# P05_Processor_Page_3_of_3.net
KiCad netlist of a schematic drawn in Altium Designer
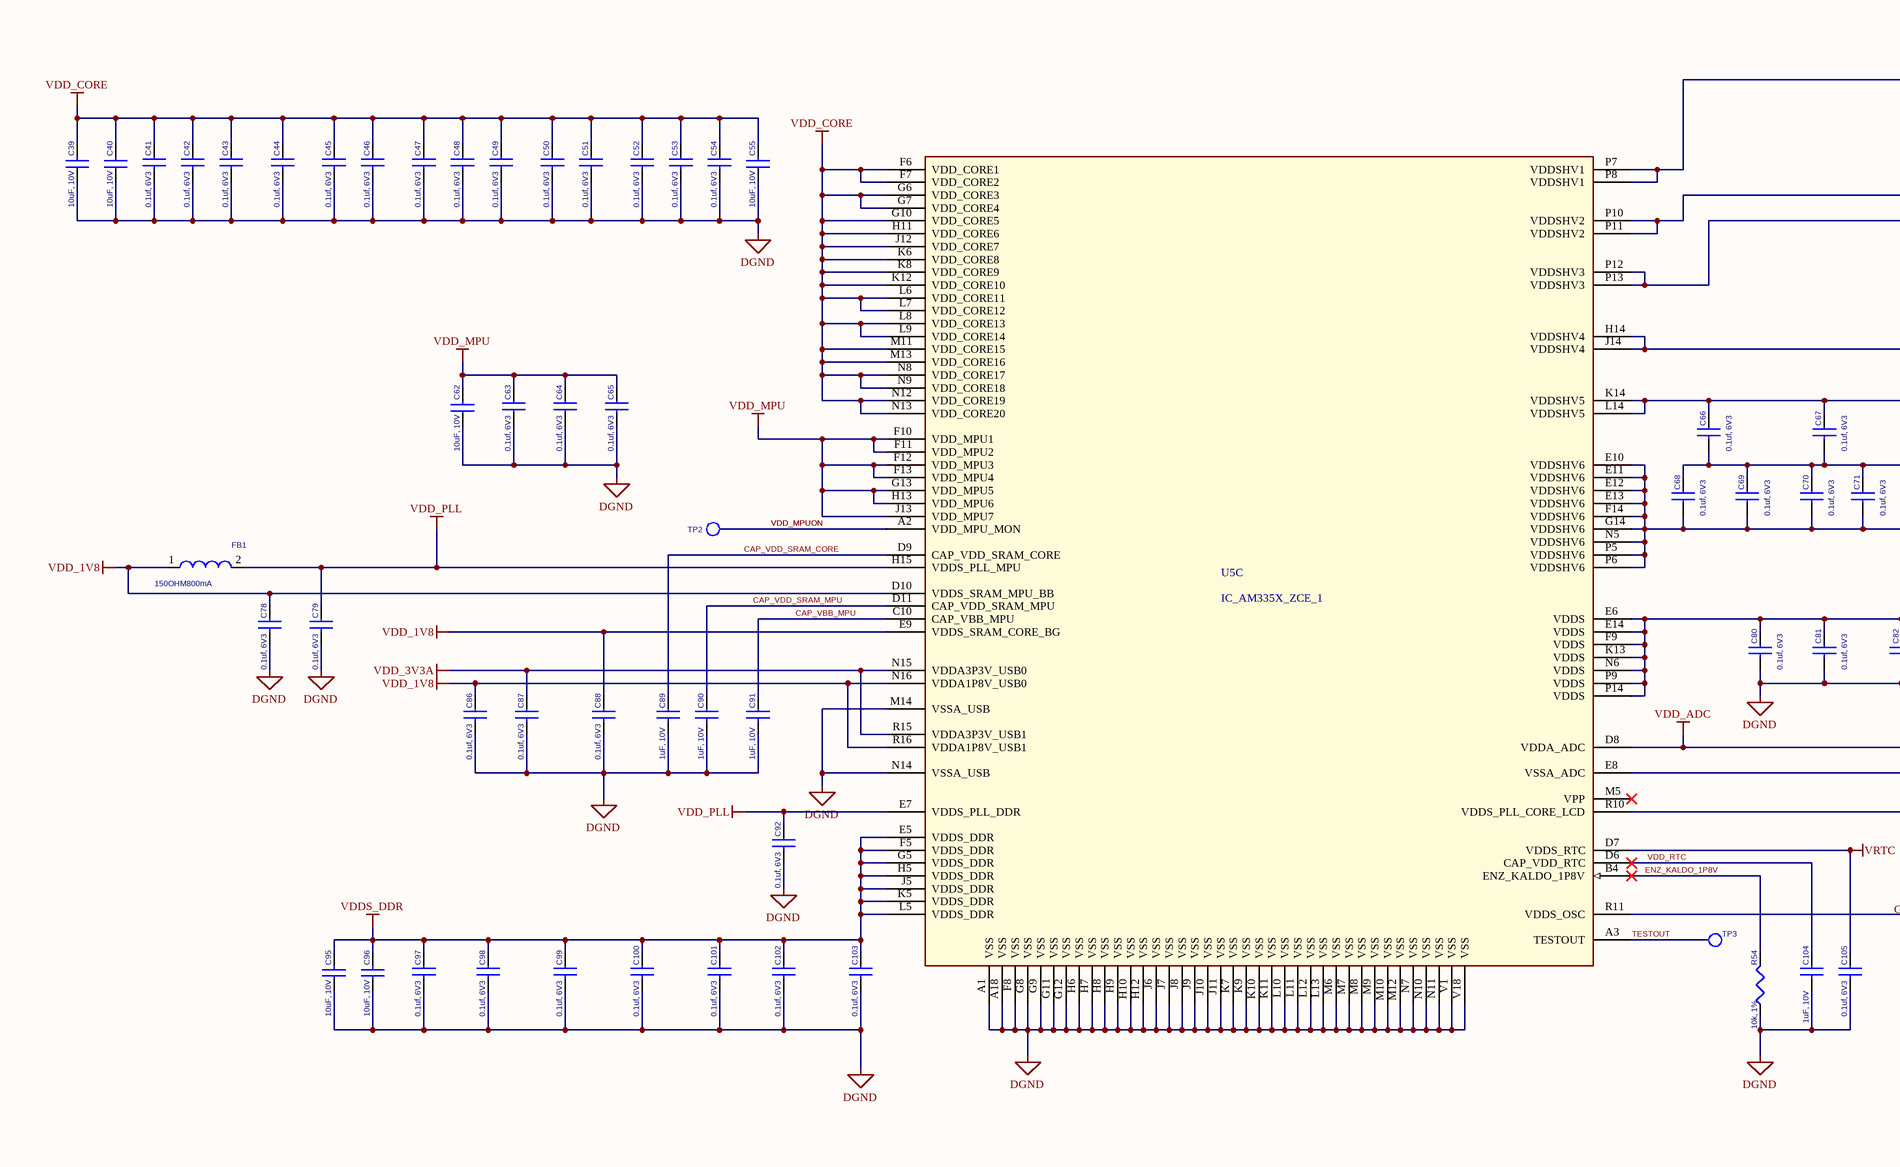
[diagram p0: P05_Processor Page 3 of 3.SchDoc, left]
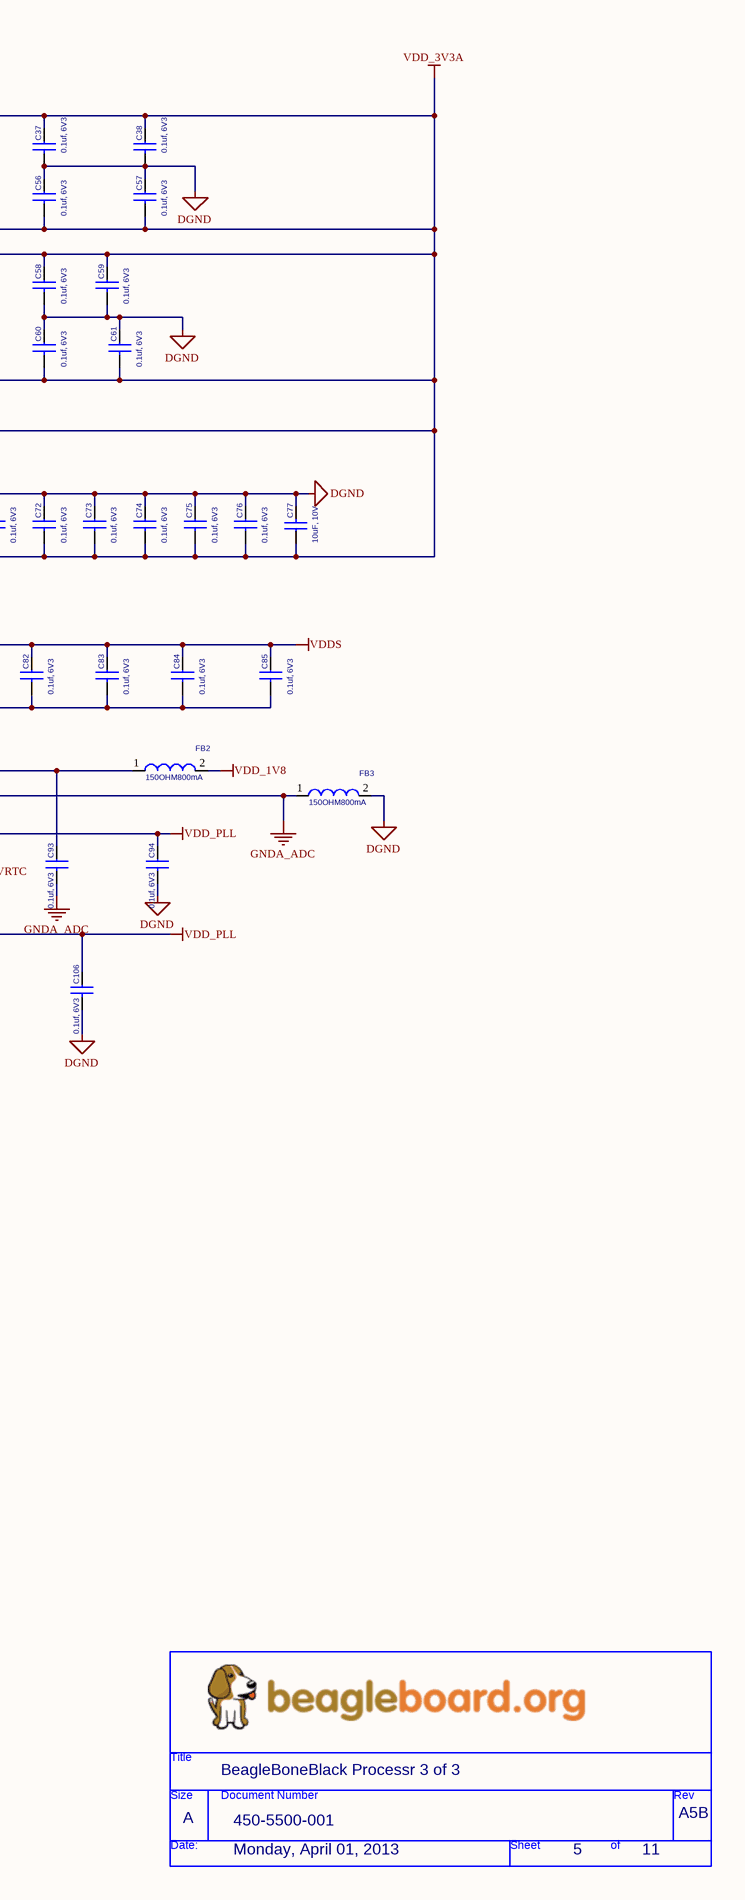
[diagram p1: P05_Processor Page 3 of 3.SchDoc, right]

(export (version "E")
  (design (tool "Eeschema 10.0.6"))
  (components
    (comp (ref "C37")
      (value "0.1uf, 6V3")
      (footprint "402")
      (description "CAP CER 0.1UF 6.3V 10% X5R 0402")
      (fields
        (field (name "MANUFACTURER") "TDK Corporation")
        (field (name "MANUFACTURER PART NUMBER") "C1005X5R0J104K050BA")
      )
      (libsource (lib "BEAGLEBONEBLACK_REV A5B") (part "CAP_0.1uF_X7R_16V_10% 0402"))
    )
    (comp (ref "C38")
      (value "0.1uf, 6V3")
      (footprint "402")
      (description "CAP CER 0.1UF 6.3V 10% X5R 0402")
      (fields
        (field (name "MANUFACTURER") "TDK Corporation")
        (field (name "MANUFACTURER PART NUMBER") "C1005X5R0J104K050BA")
      )
      (libsource (lib "BEAGLEBONEBLACK_REV A5B") (part "CAP_0.1uF_X7R_16V_10% 0402"))
    )
    (comp (ref "C39")
      (value "10uF, 10V")
      (description "CAP CER 10UF 10V Y5V 0805")
      (fields
        (field (name "MANUFACTURER") "TDK Corporation")
        (field (name "MANUFACTURER PART NUMBER") "C2012Y5V1A106Z")
      )
      (libsource (lib "BEAGLEBONEBLACK_REV A5B") (part "CAP_10uF_Y5V_10V_10%_0805"))
    )
    (comp (ref "C40")
      (value "10uF, 10V")
      (description "CAP CER 10UF 10V Y5V 0805")
      (fields
        (field (name "MANUFACTURER") "TDK Corporation")
        (field (name "MANUFACTURER PART NUMBER") "C2012Y5V1A106Z")
      )
      (libsource (lib "BEAGLEBONEBLACK_REV A5B") (part "CAP_10uF_Y5V_10V_10%_0805"))
    )
    (comp (ref "C41")
      (value "0.1uf, 6V3")
      (footprint "402")
      (description "CAP CER 0.1UF 6.3V 10% X5R 0402")
      (fields
        (field (name "MANUFACTURER") "TDK Corporation")
        (field (name "MANUFACTURER PART NUMBER") "C1005X5R0J104K050BA")
      )
      (libsource (lib "BEAGLEBONEBLACK_REV A5B") (part "CAP_0.1uF_X7R_16V_10% 0402"))
    )
    (comp (ref "C42")
      (value "0.1uf, 6V3")
      (footprint "402")
      (description "CAP CER 0.1UF 6.3V 10% X5R 0402")
      (fields
        (field (name "MANUFACTURER") "TDK Corporation")
        (field (name "MANUFACTURER PART NUMBER") "C1005X5R0J104K050BA")
      )
      (libsource (lib "BEAGLEBONEBLACK_REV A5B") (part "CAP_0.1uF_X7R_16V_10% 0402"))
    )
    (comp (ref "C43")
      (value "0.1uf, 6V3")
      (footprint "402")
      (description "CAP CER 0.1UF 6.3V 10% X5R 0402")
      (fields
        (field (name "MANUFACTURER") "TDK Corporation")
        (field (name "MANUFACTURER PART NUMBER") "C1005X5R0J104K050BA")
      )
      (libsource (lib "BEAGLEBONEBLACK_REV A5B") (part "CAP_0.1uF_X7R_16V_10% 0402"))
    )
    (comp (ref "C44")
      (value "0.1uf, 6V3")
      (footprint "402")
      (description "CAP CER 0.1UF 6.3V 10% X5R 0402")
      (fields
        (field (name "MANUFACTURER") "TDK Corporation")
        (field (name "MANUFACTURER PART NUMBER") "C1005X5R0J104K050BA")
      )
      (libsource (lib "BEAGLEBONEBLACK_REV A5B") (part "CAP_0.1uF_X7R_16V_10% 0402"))
    )
    (comp (ref "C45")
      (value "0.1uf, 6V3")
      (footprint "402")
      (description "CAP CER 0.1UF 6.3V 10% X5R 0402")
      (fields
        (field (name "MANUFACTURER") "TDK Corporation")
        (field (name "MANUFACTURER PART NUMBER") "C1005X5R0J104K050BA")
      )
      (libsource (lib "BEAGLEBONEBLACK_REV A5B") (part "CAP_0.1uF_X7R_16V_10% 0402"))
    )
    (comp (ref "C46")
      (value "0.1uf, 6V3")
      (footprint "402")
      (description "CAP CER 0.1UF 6.3V 10% X5R 0402")
      (fields
        (field (name "MANUFACTURER") "TDK Corporation")
        (field (name "MANUFACTURER PART NUMBER") "C1005X5R0J104K050BA")
      )
      (libsource (lib "BEAGLEBONEBLACK_REV A5B") (part "CAP_0.1uF_X7R_16V_10% 0402"))
    )
    (comp (ref "C47")
      (value "0.1uf, 6V3")
      (footprint "402")
      (description "CAP CER 0.1UF 6.3V 10% X5R 0402")
      (fields
        (field (name "MANUFACTURER") "TDK Corporation")
        (field (name "MANUFACTURER PART NUMBER") "C1005X5R0J104K050BA")
      )
      (libsource (lib "BEAGLEBONEBLACK_REV A5B") (part "CAP_0.1uF_X7R_16V_10% 0402"))
    )
    (comp (ref "C48")
      (value "0.1uf, 6V3")
      (footprint "402")
      (description "CAP CER 0.1UF 6.3V 10% X5R 0402")
      (fields
        (field (name "MANUFACTURER") "TDK Corporation")
        (field (name "MANUFACTURER PART NUMBER") "C1005X5R0J104K050BA")
      )
      (libsource (lib "BEAGLEBONEBLACK_REV A5B") (part "CAP_0.1uF_X7R_16V_10% 0402"))
    )
    (comp (ref "C49")
      (value "0.1uf, 6V3")
      (footprint "402")
      (description "CAP CER 0.1UF 6.3V 10% X5R 0402")
      (fields
        (field (name "MANUFACTURER") "TDK Corporation")
        (field (name "MANUFACTURER PART NUMBER") "C1005X5R0J104K050BA")
      )
      (libsource (lib "BEAGLEBONEBLACK_REV A5B") (part "CAP_0.1uF_X7R_16V_10% 0402"))
    )
    (comp (ref "C50")
      (value "0.1uf, 6V3")
      (footprint "402")
      (description "CAP CER 0.1UF 6.3V 10% X5R 0402")
      (fields
        (field (name "MANUFACTURER") "TDK Corporation")
        (field (name "MANUFACTURER PART NUMBER") "C1005X5R0J104K050BA")
      )
      (libsource (lib "BEAGLEBONEBLACK_REV A5B") (part "CAP_0.1uF_X7R_16V_10% 0402"))
    )
    (comp (ref "C51")
      (value "0.1uf, 6V3")
      (footprint "402")
      (description "CAP CER 0.1UF 6.3V 10% X5R 0402")
      (fields
        (field (name "MANUFACTURER") "TDK Corporation")
        (field (name "MANUFACTURER PART NUMBER") "C1005X5R0J104K050BA")
      )
      (libsource (lib "BEAGLEBONEBLACK_REV A5B") (part "CAP_0.1uF_X7R_16V_10% 0402"))
    )
    (comp (ref "C52")
      (value "0.1uf, 6V3")
      (footprint "402")
      (description "CAP CER 0.1UF 6.3V 10% X5R 0402")
      (fields
        (field (name "MANUFACTURER") "TDK Corporation")
        (field (name "MANUFACTURER PART NUMBER") "C1005X5R0J104K050BA")
      )
      (libsource (lib "BEAGLEBONEBLACK_REV A5B") (part "CAP_0.1uF_X7R_16V_10% 0402"))
    )
    (comp (ref "C53")
      (value "0.1uf, 6V3")
      (footprint "402")
      (description "CAP CER 0.1UF 6.3V 10% X5R 0402")
      (fields
        (field (name "MANUFACTURER") "TDK Corporation")
        (field (name "MANUFACTURER PART NUMBER") "C1005X5R0J104K050BA")
      )
      (libsource (lib "BEAGLEBONEBLACK_REV A5B") (part "CAP_0.1uF_X7R_16V_10% 0402"))
    )
    (comp (ref "C54")
      (value "0.1uf, 6V3")
      (footprint "402")
      (description "CAP CER 0.1UF 6.3V 10% X5R 0402")
      (fields
        (field (name "MANUFACTURER") "TDK Corporation")
        (field (name "MANUFACTURER PART NUMBER") "C1005X5R0J104K050BA")
      )
      (libsource (lib "BEAGLEBONEBLACK_REV A5B") (part "CAP_0.1uF_X7R_16V_10% 0402"))
    )
    (comp (ref "C55")
      (value "10uF, 10V")
      (description "CAP CER 10UF 10V Y5V 0805")
      (fields
        (field (name "MANUFACTURER") "TDK Corporation")
        (field (name "MANUFACTURER PART NUMBER") "C2012Y5V1A106Z")
      )
      (libsource (lib "BEAGLEBONEBLACK_REV A5B") (part "CAP_10uF_Y5V_10V_10%_0805"))
    )
    (comp (ref "C56")
      (value "0.1uf, 6V3")
      (footprint "402")
      (description "CAP CER 0.1UF 6.3V 10% X5R 0402")
      (fields
        (field (name "MANUFACTURER") "TDK Corporation")
        (field (name "MANUFACTURER PART NUMBER") "C1005X5R0J104K050BA")
      )
      (libsource (lib "BEAGLEBONEBLACK_REV A5B") (part "CAP_0.1uF_X7R_16V_10% 0402"))
    )
    (comp (ref "C57")
      (value "0.1uf, 6V3")
      (footprint "402")
      (description "CAP CER 0.1UF 6.3V 10% X5R 0402")
      (fields
        (field (name "MANUFACTURER") "TDK Corporation")
        (field (name "MANUFACTURER PART NUMBER") "C1005X5R0J104K050BA")
      )
      (libsource (lib "BEAGLEBONEBLACK_REV A5B") (part "CAP_0.1uF_X7R_16V_10% 0402"))
    )
    (comp (ref "C58")
      (value "0.1uf, 6V3")
      (footprint "402")
      (description "CAP CER 0.1UF 6.3V 10% X5R 0402")
      (fields
        (field (name "MANUFACTURER") "TDK Corporation")
        (field (name "MANUFACTURER PART NUMBER") "C1005X5R0J104K050BA")
      )
      (libsource (lib "BEAGLEBONEBLACK_REV A5B") (part "CAP_0.1uF_X7R_16V_10% 0402"))
    )
    (comp (ref "C59")
      (value "0.1uf, 6V3")
      (footprint "402")
      (description "CAP CER 0.1UF 6.3V 10% X5R 0402")
      (fields
        (field (name "MANUFACTURER") "TDK Corporation")
        (field (name "MANUFACTURER PART NUMBER") "C1005X5R0J104K050BA")
      )
      (libsource (lib "BEAGLEBONEBLACK_REV A5B") (part "CAP_0.1uF_X7R_16V_10% 0402"))
    )
    (comp (ref "C60")
      (value "0.1uf, 6V3")
      (footprint "402")
      (description "CAP CER 0.1UF 6.3V 10% X5R 0402")
      (fields
        (field (name "MANUFACTURER") "TDK Corporation")
        (field (name "MANUFACTURER PART NUMBER") "C1005X5R0J104K050BA")
      )
      (libsource (lib "BEAGLEBONEBLACK_REV A5B") (part "CAP_0.1uF_X7R_16V_10% 0402"))
    )
    (comp (ref "C61")
      (value "0.1uf, 6V3")
      (footprint "402")
      (description "CAP CER 0.1UF 6.3V 10% X5R 0402")
      (fields
        (field (name "MANUFACTURER") "TDK Corporation")
        (field (name "MANUFACTURER PART NUMBER") "C1005X5R0J104K050BA")
      )
      (libsource (lib "BEAGLEBONEBLACK_REV A5B") (part "CAP_0.1uF_X7R_16V_10% 0402"))
    )
    (comp (ref "C62")
      (value "10uF, 10V")
      (description "CAP CER 10UF 10V Y5V 0805")
      (fields
        (field (name "MANUFACTURER") "TDK Corporation")
        (field (name "MANUFACTURER PART NUMBER") "C2012Y5V1A106Z")
      )
      (libsource (lib "BEAGLEBONEBLACK_REV A5B") (part "CAP_10uF_Y5V_10V_10%_0805"))
    )
    (comp (ref "C63")
      (value "0.1uf, 6V3")
      (footprint "402")
      (description "CAP CER 0.1UF 6.3V 10% X5R 0402")
      (fields
        (field (name "MANUFACTURER") "TDK Corporation")
        (field (name "MANUFACTURER PART NUMBER") "C1005X5R0J104K050BA")
      )
      (libsource (lib "BEAGLEBONEBLACK_REV A5B") (part "CAP_0.1uF_X7R_16V_10% 0402"))
    )
    (comp (ref "C64")
      (value "0.1uf, 6V3")
      (footprint "402")
      (description "CAP CER 0.1UF 6.3V 10% X5R 0402")
      (fields
        (field (name "MANUFACTURER") "TDK Corporation")
        (field (name "MANUFACTURER PART NUMBER") "C1005X5R0J104K050BA")
      )
      (libsource (lib "BEAGLEBONEBLACK_REV A5B") (part "CAP_0.1uF_X7R_16V_10% 0402"))
    )
    (comp (ref "C65")
      (value "0.1uf, 6V3")
      (footprint "402")
      (description "CAP CER 0.1UF 6.3V 10% X5R 0402")
      (fields
        (field (name "MANUFACTURER") "TDK Corporation")
        (field (name "MANUFACTURER PART NUMBER") "C1005X5R0J104K050BA")
      )
      (libsource (lib "BEAGLEBONEBLACK_REV A5B") (part "CAP_0.1uF_X7R_16V_10% 0402"))
    )
    (comp (ref "C66")
      (value "0.1uf, 6V3")
      (footprint "402")
      (description "CAP CER 0.1UF 6.3V 10% X5R 0402")
      (fields
        (field (name "MANUFACTURER") "TDK Corporation")
        (field (name "MANUFACTURER PART NUMBER") "C1005X5R0J104K050BA")
      )
      (libsource (lib "BEAGLEBONEBLACK_REV A5B") (part "CAP_0.1uF_X7R_16V_10% 0402"))
    )
    (comp (ref "C67")
      (value "0.1uf, 6V3")
      (footprint "402")
      (description "CAP CER 0.1UF 6.3V 10% X5R 0402")
      (fields
        (field (name "MANUFACTURER") "TDK Corporation")
        (field (name "MANUFACTURER PART NUMBER") "C1005X5R0J104K050BA")
      )
      (libsource (lib "BEAGLEBONEBLACK_REV A5B") (part "CAP_0.1uF_X7R_16V_10% 0402"))
    )
    (comp (ref "C68")
      (value "0.1uf, 6V3")
      (footprint "402")
      (description "CAP CER 0.1UF 6.3V 10% X5R 0402")
      (fields
        (field (name "MANUFACTURER") "TDK Corporation")
        (field (name "MANUFACTURER PART NUMBER") "C1005X5R0J104K050BA")
      )
      (libsource (lib "BEAGLEBONEBLACK_REV A5B") (part "CAP_0.1uF_X7R_16V_10% 0402"))
    )
    (comp (ref "C69")
      (value "0.1uf, 6V3")
      (footprint "402")
      (description "CAP CER 0.1UF 6.3V 10% X5R 0402")
      (fields
        (field (name "MANUFACTURER") "TDK Corporation")
        (field (name "MANUFACTURER PART NUMBER") "C1005X5R0J104K050BA")
      )
      (libsource (lib "BEAGLEBONEBLACK_REV A5B") (part "CAP_0.1uF_X7R_16V_10% 0402"))
    )
    (comp (ref "C70")
      (value "0.1uf, 6V3")
      (footprint "402")
      (description "CAP CER 0.1UF 6.3V 10% X5R 0402")
      (fields
        (field (name "MANUFACTURER") "TDK Corporation")
        (field (name "MANUFACTURER PART NUMBER") "C1005X5R0J104K050BA")
      )
      (libsource (lib "BEAGLEBONEBLACK_REV A5B") (part "CAP_0.1uF_X7R_16V_10% 0402"))
    )
    (comp (ref "C71")
      (value "0.1uf, 6V3")
      (footprint "402")
      (description "CAP CER 0.1UF 6.3V 10% X5R 0402")
      (fields
        (field (name "MANUFACTURER") "TDK Corporation")
        (field (name "MANUFACTURER PART NUMBER") "C1005X5R0J104K050BA")
      )
      (libsource (lib "BEAGLEBONEBLACK_REV A5B") (part "CAP_0.1uF_X7R_16V_10% 0402"))
    )
    (comp (ref "C72")
      (value "0.1uf, 6V3")
      (footprint "402")
      (description "CAP CER 0.1UF 6.3V 10% X5R 0402")
      (fields
        (field (name "MANUFACTURER") "TDK Corporation")
        (field (name "MANUFACTURER PART NUMBER") "C1005X5R0J104K050BA")
      )
      (libsource (lib "BEAGLEBONEBLACK_REV A5B") (part "CAP_0.1uF_X7R_16V_10% 0402"))
    )
    (comp (ref "C73")
      (value "0.1uf, 6V3")
      (footprint "402")
      (description "CAP CER 0.1UF 6.3V 10% X5R 0402")
      (fields
        (field (name "MANUFACTURER") "TDK Corporation")
        (field (name "MANUFACTURER PART NUMBER") "C1005X5R0J104K050BA")
      )
      (libsource (lib "BEAGLEBONEBLACK_REV A5B") (part "CAP_0.1uF_X7R_16V_10% 0402"))
    )
    (comp (ref "C74")
      (value "0.1uf, 6V3")
      (footprint "402")
      (description "CAP CER 0.1UF 6.3V 10% X5R 0402")
      (fields
        (field (name "MANUFACTURER") "TDK Corporation")
        (field (name "MANUFACTURER PART NUMBER") "C1005X5R0J104K050BA")
      )
      (libsource (lib "BEAGLEBONEBLACK_REV A5B") (part "CAP_0.1uF_X7R_16V_10% 0402"))
    )
    (comp (ref "C75")
      (value "0.1uf, 6V3")
      (footprint "402")
      (description "CAP CER 0.1UF 6.3V 10% X5R 0402")
      (fields
        (field (name "MANUFACTURER") "TDK Corporation")
        (field (name "MANUFACTURER PART NUMBER") "C1005X5R0J104K050BA")
      )
      (libsource (lib "BEAGLEBONEBLACK_REV A5B") (part "CAP_0.1uF_X7R_16V_10% 0402"))
    )
    (comp (ref "C76")
      (value "0.1uf, 6V3")
      (footprint "402")
      (description "CAP CER 0.1UF 6.3V 10% X5R 0402")
      (fields
        (field (name "MANUFACTURER") "TDK Corporation")
        (field (name "MANUFACTURER PART NUMBER") "C1005X5R0J104K050BA")
      )
      (libsource (lib "BEAGLEBONEBLACK_REV A5B") (part "CAP_0.1uF_X7R_16V_10% 0402"))
    )
    (comp (ref "C77")
      (value "10uF, 10V")
      (description "CAP CER 10UF 10V Y5V 0805")
      (fields
        (field (name "MANUFACTURER") "TDK Corporation")
        (field (name "MANUFACTURER PART NUMBER") "C2012Y5V1A106Z")
      )
      (libsource (lib "BEAGLEBONEBLACK_REV A5B") (part "CAP_10uF_Y5V_10V_10%_0805"))
    )
    (comp (ref "C78")
      (value "0.1uf, 6V3")
      (footprint "402")
      (description "CAP CER 0.1UF 6.3V 10% X5R 0402")
      (fields
        (field (name "MANUFACTURER") "TDK Corporation")
        (field (name "MANUFACTURER PART NUMBER") "C1005X5R0J104K050BA")
      )
      (libsource (lib "BEAGLEBONEBLACK_REV A5B") (part "CAP_0.1uF_X7R_16V_10% 0402"))
    )
    (comp (ref "C79")
      (value "0.1uf, 6V3")
      (footprint "402")
      (description "CAP CER 0.1UF 6.3V 10% X5R 0402")
      (fields
        (field (name "MANUFACTURER") "TDK Corporation")
        (field (name "MANUFACTURER PART NUMBER") "C1005X5R0J104K050BA")
      )
      (libsource (lib "BEAGLEBONEBLACK_REV A5B") (part "CAP_0.1uF_X7R_16V_10% 0402"))
    )
    (comp (ref "C80")
      (value "0.1uf, 6V3")
      (footprint "402")
      (description "CAP CER 0.1UF 6.3V 10% X5R 0402")
      (fields
        (field (name "MANUFACTURER") "TDK Corporation")
        (field (name "MANUFACTURER PART NUMBER") "C1005X5R0J104K050BA")
      )
      (libsource (lib "BEAGLEBONEBLACK_REV A5B") (part "CAP_0.1uF_X7R_16V_10% 0402"))
    )
    (comp (ref "C81")
      (value "0.1uf, 6V3")
      (footprint "402")
      (description "CAP CER 0.1UF 6.3V 10% X5R 0402")
      (fields
        (field (name "MANUFACTURER") "TDK Corporation")
        (field (name "MANUFACTURER PART NUMBER") "C1005X5R0J104K050BA")
      )
      (libsource (lib "BEAGLEBONEBLACK_REV A5B") (part "CAP_0.1uF_X7R_16V_10% 0402"))
    )
    (comp (ref "C82")
      (value "0.1uf, 6V3")
      (footprint "402")
      (description "CAP CER 0.1UF 6.3V 10% X5R 0402")
      (fields
        (field (name "MANUFACTURER") "TDK Corporation")
        (field (name "MANUFACTURER PART NUMBER") "C1005X5R0J104K050BA")
      )
      (libsource (lib "BEAGLEBONEBLACK_REV A5B") (part "CAP_0.1uF_X7R_16V_10% 0402"))
    )
    (comp (ref "C83")
      (value "0.1uf, 6V3")
      (footprint "402")
      (description "CAP CER 0.1UF 6.3V 10% X5R 0402")
      (fields
        (field (name "MANUFACTURER") "TDK Corporation")
        (field (name "MANUFACTURER PART NUMBER") "C1005X5R0J104K050BA")
      )
      (libsource (lib "BEAGLEBONEBLACK_REV A5B") (part "CAP_0.1uF_X7R_16V_10% 0402"))
    )
    (comp (ref "C84")
      (value "0.1uf, 6V3")
      (footprint "402")
      (description "CAP CER 0.1UF 6.3V 10% X5R 0402")
      (fields
        (field (name "MANUFACTURER") "TDK Corporation")
        (field (name "MANUFACTURER PART NUMBER") "C1005X5R0J104K050BA")
      )
      (libsource (lib "BEAGLEBONEBLACK_REV A5B") (part "CAP_0.1uF_X7R_16V_10% 0402"))
    )
    (comp (ref "C85")
      (value "0.1uf, 6V3")
      (footprint "402")
      (description "CAP CER 0.1UF 6.3V 10% X5R 0402")
      (fields
        (field (name "MANUFACTURER") "TDK Corporation")
        (field (name "MANUFACTURER PART NUMBER") "C1005X5R0J104K050BA")
      )
      (libsource (lib "BEAGLEBONEBLACK_REV A5B") (part "CAP_0.1uF_X7R_16V_10% 0402"))
    )
    (comp (ref "C86")
      (value "0.1uf, 6V3")
      (footprint "402")
      (description "CAP CER 0.1UF 6.3V 10% X5R 0402")
      (fields
        (field (name "MANUFACTURER") "TDK Corporation")
        (field (name "MANUFACTURER PART NUMBER") "C1005X5R0J104K050BA")
      )
      (libsource (lib "BEAGLEBONEBLACK_REV A5B") (part "CAP_0.1uF_X7R_16V_10% 0402"))
    )
    (comp (ref "C87")
      (value "0.1uf, 6V3")
      (footprint "402")
      (description "CAP CER 0.1UF 6.3V 10% X5R 0402")
      (fields
        (field (name "MANUFACTURER") "TDK Corporation")
        (field (name "MANUFACTURER PART NUMBER") "C1005X5R0J104K050BA")
      )
      (libsource (lib "BEAGLEBONEBLACK_REV A5B") (part "CAP_0.1uF_X7R_16V_10% 0402"))
    )
    (comp (ref "C88")
      (value "0.1uf, 6V3")
      (footprint "402")
      (description "CAP CER 0.1UF 6.3V 10% X5R 0402")
      (fields
        (field (name "MANUFACTURER") "TDK Corporation")
        (field (name "MANUFACTURER PART NUMBER") "C1005X5R0J104K050BA")
      )
      (libsource (lib "BEAGLEBONEBLACK_REV A5B") (part "CAP_0.1uF_X7R_16V_10% 0402"))
    )
    (comp (ref "C89")
      (value "1uF, 10V")
      (footprint "402")
      (description "CAP CER 1UF 10V 10% X5R 0402")
      (fields
        (field (name "MANUFACTURER") "AVX Corporation")
        (field (name "MANUFACTURER PART NUMBER") "0402ZD105KAT2A")
      )
      (libsource (lib "BEAGLEBONEBLACK_REV A5B") (part "CAP_1.0UF_X5R_10V_10%_0402"))
    )
    (comp (ref "C90")
      (value "1uF, 10V")
      (footprint "402")
      (description "CAP CER 1UF 10V 10% X5R 0402")
      (fields
        (field (name "MANUFACTURER") "AVX Corporation")
        (field (name "MANUFACTURER PART NUMBER") "0402ZD105KAT2A")
      )
      (libsource (lib "BEAGLEBONEBLACK_REV A5B") (part "CAP_1.0UF_X5R_10V_10%_0402"))
    )
    (comp (ref "C91")
      (value "1uF, 10V")
      (footprint "402")
      (description "CAP CER 1UF 10V 10% X5R 0402")
      (fields
        (field (name "MANUFACTURER") "AVX Corporation")
        (field (name "MANUFACTURER PART NUMBER") "0402ZD105KAT2A")
      )
      (libsource (lib "BEAGLEBONEBLACK_REV A5B") (part "CAP_1.0UF_X5R_10V_10%_0402"))
    )
    (comp (ref "C92")
      (value "0.1uf, 6V3")
      (footprint "402")
      (description "CAP CER 0.1UF 6.3V 10% X5R 0402")
      (fields
        (field (name "MANUFACTURER") "TDK Corporation")
        (field (name "MANUFACTURER PART NUMBER") "C1005X5R0J104K050BA")
      )
      (libsource (lib "BEAGLEBONEBLACK_REV A5B") (part "CAP_0.1uF_X7R_16V_10% 0402"))
    )
    (comp (ref "C93")
      (value "0.1uf, 6V3")
      (footprint "402")
      (description "CAP CER 0.1UF 6.3V 10% X5R 0402")
      (fields
        (field (name "MANUFACTURER") "TDK Corporation")
        (field (name "MANUFACTURER PART NUMBER") "C1005X5R0J104K050BA")
      )
      (libsource (lib "BEAGLEBONEBLACK_REV A5B") (part "CAP_0.1uF_X7R_16V_10% 0402"))
    )
    (comp (ref "C94")
      (value "0.1uf, 6V3")
      (footprint "402")
      (description "CAP CER 0.1UF 6.3V 10% X5R 0402")
      (fields
        (field (name "MANUFACTURER") "TDK Corporation")
        (field (name "MANUFACTURER PART NUMBER") "C1005X5R0J104K050BA")
      )
      (libsource (lib "BEAGLEBONEBLACK_REV A5B") (part "CAP_0.1uF_X7R_16V_10% 0402"))
    )
    (comp (ref "C95")
      (value "10uF, 10V")
      (description "CAP CER 10UF 10V Y5V 0805")
      (fields
        (field (name "MANUFACTURER") "TDK Corporation")
        (field (name "MANUFACTURER PART NUMBER") "C2012Y5V1A106Z")
      )
      (libsource (lib "BEAGLEBONEBLACK_REV A5B") (part "CAP_10uF_Y5V_10V_10%_0805"))
    )
    (comp (ref "C96")
      (value "10uF, 10V")
      (description "CAP CER 10UF 10V Y5V 0805")
      (fields
        (field (name "MANUFACTURER") "TDK Corporation")
        (field (name "MANUFACTURER PART NUMBER") "C2012Y5V1A106Z")
      )
      (libsource (lib "BEAGLEBONEBLACK_REV A5B") (part "CAP_10uF_Y5V_10V_10%_0805"))
    )
    (comp (ref "C97")
      (value "0.1uf, 6V3")
      (footprint "402")
      (description "CAP CER 0.1UF 6.3V 10% X5R 0402")
      (fields
        (field (name "MANUFACTURER") "TDK Corporation")
        (field (name "MANUFACTURER PART NUMBER") "C1005X5R0J104K050BA")
      )
      (libsource (lib "BEAGLEBONEBLACK_REV A5B") (part "CAP_0.1uF_X7R_16V_10% 0402"))
    )
    (comp (ref "C98")
      (value "0.1uf, 6V3")
      (footprint "402")
      (description "CAP CER 0.1UF 6.3V 10% X5R 0402")
      (fields
        (field (name "MANUFACTURER") "TDK Corporation")
        (field (name "MANUFACTURER PART NUMBER") "C1005X5R0J104K050BA")
      )
      (libsource (lib "BEAGLEBONEBLACK_REV A5B") (part "CAP_0.1uF_X7R_16V_10% 0402"))
    )
    (comp (ref "C99")
      (value "0.1uf, 6V3")
      (footprint "402")
      (description "CAP CER 0.1UF 6.3V 10% X5R 0402")
      (fields
        (field (name "MANUFACTURER") "TDK Corporation")
        (field (name "MANUFACTURER PART NUMBER") "C1005X5R0J104K050BA")
      )
      (libsource (lib "BEAGLEBONEBLACK_REV A5B") (part "CAP_0.1uF_X7R_16V_10% 0402"))
    )
    (comp (ref "C100")
      (value "0.1uf, 6V3")
      (footprint "402")
      (description "CAP CER 0.1UF 6.3V 10% X5R 0402")
      (fields
        (field (name "MANUFACTURER") "TDK Corporation")
        (field (name "MANUFACTURER PART NUMBER") "C1005X5R0J104K050BA")
      )
      (libsource (lib "BEAGLEBONEBLACK_REV A5B") (part "CAP_0.1uF_X7R_16V_10% 0402"))
    )
    (comp (ref "C101")
      (value "0.1uf, 6V3")
      (footprint "402")
      (description "CAP CER 0.1UF 6.3V 10% X5R 0402")
      (fields
        (field (name "MANUFACTURER") "TDK Corporation")
        (field (name "MANUFACTURER PART NUMBER") "C1005X5R0J104K050BA")
      )
      (libsource (lib "BEAGLEBONEBLACK_REV A5B") (part "CAP_0.1uF_X7R_16V_10% 0402"))
    )
    (comp (ref "C102")
      (value "0.1uf, 6V3")
      (footprint "402")
      (description "CAP CER 0.1UF 6.3V 10% X5R 0402")
      (fields
        (field (name "MANUFACTURER") "TDK Corporation")
        (field (name "MANUFACTURER PART NUMBER") "C1005X5R0J104K050BA")
      )
      (libsource (lib "BEAGLEBONEBLACK_REV A5B") (part "CAP_0.1uF_X7R_16V_10% 0402"))
    )
    (comp (ref "C103")
      (value "0.1uf, 6V3")
      (footprint "402")
      (description "CAP CER 0.1UF 6.3V 10% X5R 0402")
      (fields
        (field (name "MANUFACTURER") "TDK Corporation")
        (field (name "MANUFACTURER PART NUMBER") "C1005X5R0J104K050BA")
      )
      (libsource (lib "BEAGLEBONEBLACK_REV A5B") (part "CAP_0.1uF_X7R_16V_10% 0402"))
    )
    (comp (ref "C104")
      (value "1uF, 10V")
      (footprint "402")
      (description "CAP CER 1UF 10V 10% X5R 0402")
      (fields
        (field (name "MANUFACTURER") "AVX Corporation")
        (field (name "MANUFACTURER PART NUMBER") "0402ZD105KAT2A")
      )
      (libsource (lib "BEAGLEBONEBLACK_REV A5B") (part "CAP_1.0UF_X5R_10V_10%_0402"))
    )
    (comp (ref "C105")
      (value "0.1uf, 6V3")
      (footprint "402")
      (description "CAP CER 0.1UF 6.3V 10% X5R 0402")
      (fields
        (field (name "MANUFACTURER") "TDK Corporation")
        (field (name "MANUFACTURER PART NUMBER") "C1005X5R0J104K050BA")
      )
      (libsource (lib "BEAGLEBONEBLACK_REV A5B") (part "CAP_0.1uF_X7R_16V_10% 0402"))
    )
    (comp (ref "C106")
      (value "0.1uf, 6V3")
      (footprint "402")
      (description "CAP CER 0.1UF 6.3V 10% X5R 0402")
      (fields
        (field (name "MANUFACTURER") "TDK Corporation")
        (field (name "MANUFACTURER PART NUMBER") "C1005X5R0J104K050BA")
      )
      (libsource (lib "BEAGLEBONEBLACK_REV A5B") (part "CAP_0.1uF_X7R_16V_10% 0402"))
    )
    (comp (ref "FB1")
      (value "150OHM800mA")
      (footprint "SM-7351-IND-0805")
      (description "FERRITE 800MA 150 OHM 0805 SMD")
      (fields (field (name "MFR") "Steward") (field (name "TIINTPARTNUMBER") "1L0010"))
      (libsource (lib "BEAGLEBONEBLACK_REV A5B") (part "FER_180_200_0"))
    )
    (comp (ref "FB2")
      (value "150OHM800mA")
      (footprint "SM-7351-IND-0805")
      (description "FERRITE 800MA 150 OHM 0805 SMD")
      (fields (field (name "MFR") "Steward") (field (name "TIINTPARTNUMBER") "1L0010"))
      (libsource (lib "BEAGLEBONEBLACK_REV A5B") (part "FER_180_200_0"))
    )
    (comp (ref "FB3")
      (value "150OHM800mA")
      (footprint "SM-7351-IND-0805")
      (description "FERRITE 800MA 150 OHM 0805 SMD")
      (fields (field (name "MFR") "Steward") (field (name "TIINTPARTNUMBER") "1L0010"))
      (libsource (lib "BEAGLEBONEBLACK_REV A5B") (part "FER_180_200_0"))
    )
    (comp (ref "R54")
      (value "10k, 1%")
      (footprint "402")
      (description "RES 10K OHM 1/16W 5% 0402 SMD")
      (fields
        (field (name "MANUFACTURER") "Rohm Semiconductor")
        (field (name "MANUFACTURER PART NUMBER") "MCR01MZPJ103")
      )
      (libsource (lib "BEAGLEBONEBLACK_REV A5B") (part "RES_10K_1/16W_1%_0402"))
    )
    (comp (ref "TP2") (value "TESTPT1") (libsource (lib "BEAGLEBONEBLACK_REV A5B") (part "TESTPT1")))
    (comp (ref "TP3") (value "TESTPT1") (libsource (lib "BEAGLEBONEBLACK_REV A5B") (part "TESTPT1")))
    (comp (ref "U5")
      (value "IC_AM335X_ZCE_1")
      (footprint "am33xx_15x15")
      (description "SubArctic Cortex A8 Processor 15x15")
      (fields (field (name "MFR") "TI") (field (name "TIINTPARTNUMBER") "1A0242"))
      (libsource (lib "BEAGLEBONEBLACK_REV A5B") (part "IC_AM335X_ZCE_1"))
    )
  )
  (nets
    (net (code "1") (name "/CAP_VBB_MPU") (class "Default")
      (node (ref "C91") (pin "1") (pinfunction "1_1") (pintype "passive"))
      (node (ref "U5") (pin "C10") (pinfunction "CAP_VBB_MPU_C10") (pintype "passive"))
    )
    (net (code "2") (name "/CAP_VDD_SRAM_CORE") (class "Default")
      (node (ref "C89") (pin "1") (pinfunction "1_1") (pintype "passive"))
      (node (ref "U5") (pin "D9") (pinfunction "CAP_VDD_SRAM_CORE_D9") (pintype "power_in"))
    )
    (net (code "3") (name "/CAP_VDD_SRAM_MPU") (class "Default")
      (node (ref "C90") (pin "1") (pinfunction "1_1") (pintype "passive"))
      (node (ref "U5") (pin "D11") (pinfunction "CAP_VDD_SRAM_MPU_D11") (pintype "power_in"))
    )
    (net (code "4") (name "/ENZ_KALDO_1P8V") (class "Default")
      (node (ref "R54") (pin "2") (pinfunction "2_2") (pintype "passive"))
      (node (ref "U5") (pin "B4") (pinfunction "ENZ_KALDO_1P8V_B4") (pintype "input"))
    )
    (net (code "5") (name "/TESTOUT") (class "Default")
      (node (ref "TP3") (pin "1") (pinfunction "TP_1") (pintype "passive"))
      (node (ref "U5") (pin "A3") (pinfunction "TESTOUT_A3") (pintype "passive"))
    )
    (net (code "6") (name "/VDD_MPUON") (class "Default")
      (node (ref "TP2") (pin "1") (pinfunction "TP_1") (pintype "passive"))
      (node (ref "U5") (pin "A2") (pinfunction "VDD_MPU_MON_A2") (pintype "passive"))
    )
    (net (code "7") (name "/VDD_RTC") (class "Default")
      (node (ref "C104") (pin "1") (pinfunction "1_1") (pintype "passive"))
      (node (ref "U5") (pin "D6") (pinfunction "CAP_VDD_RTC_D6") (pintype "power_in"))
    )
    (net (code "8") (name "DGND") (class "Default")
      (node (ref "C100") (pin "2") (pinfunction "2_2") (pintype "passive"))
      (node (ref "C101") (pin "2") (pinfunction "2_2") (pintype "passive"))
      (node (ref "C102") (pin "2") (pinfunction "2_2") (pintype "passive"))
      (node (ref "C103") (pin "2") (pinfunction "2_2") (pintype "passive"))
      (node (ref "C104") (pin "2") (pinfunction "2_2") (pintype "passive"))
      (node (ref "C105") (pin "2") (pinfunction "2_2") (pintype "passive"))
      (node (ref "C106") (pin "2") (pinfunction "2_2") (pintype "passive"))
      (node (ref "C37") (pin "2") (pinfunction "2_2") (pintype "passive"))
      (node (ref "C38") (pin "2") (pinfunction "2_2") (pintype "passive"))
      (node (ref "C39") (pin "1") (pinfunction "1_1") (pintype "passive"))
      (node (ref "C40") (pin "1") (pinfunction "1_1") (pintype "passive"))
      (node (ref "C41") (pin "2") (pinfunction "2_2") (pintype "passive"))
      (node (ref "C42") (pin "2") (pinfunction "2_2") (pintype "passive"))
      (node (ref "C43") (pin "2") (pinfunction "2_2") (pintype "passive"))
      (node (ref "C44") (pin "2") (pinfunction "2_2") (pintype "passive"))
      (node (ref "C45") (pin "2") (pinfunction "2_2") (pintype "passive"))
      (node (ref "C46") (pin "2") (pinfunction "2_2") (pintype "passive"))
      (node (ref "C47") (pin "2") (pinfunction "2_2") (pintype "passive"))
      (node (ref "C48") (pin "2") (pinfunction "2_2") (pintype "passive"))
      (node (ref "C49") (pin "2") (pinfunction "2_2") (pintype "passive"))
      (node (ref "C50") (pin "2") (pinfunction "2_2") (pintype "passive"))
      (node (ref "C51") (pin "2") (pinfunction "2_2") (pintype "passive"))
      (node (ref "C52") (pin "2") (pinfunction "2_2") (pintype "passive"))
      (node (ref "C53") (pin "2") (pinfunction "2_2") (pintype "passive"))
      (node (ref "C54") (pin "2") (pinfunction "2_2") (pintype "passive"))
      (node (ref "C55") (pin "1") (pinfunction "1_1") (pintype "passive"))
      (node (ref "C56") (pin "1") (pinfunction "1_1") (pintype "passive"))
      (node (ref "C57") (pin "1") (pinfunction "1_1") (pintype "passive"))
      (node (ref "C58") (pin "2") (pinfunction "2_2") (pintype "passive"))
      (node (ref "C59") (pin "2") (pinfunction "2_2") (pintype "passive"))
      (node (ref "C60") (pin "1") (pinfunction "1_1") (pintype "passive"))
      (node (ref "C61") (pin "1") (pinfunction "1_1") (pintype "passive"))
      (node (ref "C62") (pin "1") (pinfunction "1_1") (pintype "passive"))
      (node (ref "C63") (pin "2") (pinfunction "2_2") (pintype "passive"))
      (node (ref "C64") (pin "2") (pinfunction "2_2") (pintype "passive"))
      (node (ref "C65") (pin "2") (pinfunction "2_2") (pintype "passive"))
      (node (ref "C66") (pin "2") (pinfunction "2_2") (pintype "passive"))
      (node (ref "C67") (pin "2") (pinfunction "2_2") (pintype "passive"))
      (node (ref "C68") (pin "1") (pinfunction "1_1") (pintype "passive"))
      (node (ref "C69") (pin "1") (pinfunction "1_1") (pintype "passive"))
      (node (ref "C70") (pin "1") (pinfunction "1_1") (pintype "passive"))
      (node (ref "C71") (pin "1") (pinfunction "1_1") (pintype "passive"))
      (node (ref "C72") (pin "1") (pinfunction "1_1") (pintype "passive"))
      (node (ref "C73") (pin "1") (pinfunction "1_1") (pintype "passive"))
      (node (ref "C74") (pin "1") (pinfunction "1_1") (pintype "passive"))
      (node (ref "C75") (pin "1") (pinfunction "1_1") (pintype "passive"))
      (node (ref "C76") (pin "1") (pinfunction "1_1") (pintype "passive"))
      (node (ref "C77") (pin "2") (pinfunction "2_2") (pintype "passive"))
      (node (ref "C78") (pin "2") (pinfunction "2_2") (pintype "passive"))
      (node (ref "C79") (pin "2") (pinfunction "2_2") (pintype "passive"))
      (node (ref "C80") (pin "2") (pinfunction "2_2") (pintype "passive"))
      (node (ref "C81") (pin "2") (pinfunction "2_2") (pintype "passive"))
      (node (ref "C82") (pin "2") (pinfunction "2_2") (pintype "passive"))
      (node (ref "C83") (pin "2") (pinfunction "2_2") (pintype "passive"))
      (node (ref "C84") (pin "2") (pinfunction "2_2") (pintype "passive"))
      (node (ref "C85") (pin "2") (pinfunction "2_2") (pintype "passive"))
      (node (ref "C86") (pin "2") (pinfunction "2_2") (pintype "passive"))
      (node (ref "C87") (pin "2") (pinfunction "2_2") (pintype "passive"))
      (node (ref "C88") (pin "2") (pinfunction "2_2") (pintype "passive"))
      (node (ref "C89") (pin "2") (pinfunction "2_2") (pintype "passive"))
      (node (ref "C90") (pin "2") (pinfunction "2_2") (pintype "passive"))
      (node (ref "C91") (pin "2") (pinfunction "2_2") (pintype "passive"))
      (node (ref "C92") (pin "2") (pinfunction "2_2") (pintype "passive"))
      (node (ref "C94") (pin "2") (pinfunction "2_2") (pintype "passive"))
      (node (ref "C95") (pin "1") (pinfunction "1_1") (pintype "passive"))
      (node (ref "C96") (pin "1") (pinfunction "1_1") (pintype "passive"))
      (node (ref "C97") (pin "2") (pinfunction "2_2") (pintype "passive"))
      (node (ref "C98") (pin "2") (pinfunction "2_2") (pintype "passive"))
      (node (ref "C99") (pin "2") (pinfunction "2_2") (pintype "passive"))
      (node (ref "FB3") (pin "2") (pinfunction "2_2") (pintype "passive"))
      (node (ref "R54") (pin "1") (pinfunction "1_1") (pintype "passive"))
      (node (ref "U5") (pin "A1") (pinfunction "VSS_A1") (pintype "power_in"))
      (node (ref "U5") (pin "A18") (pinfunction "VSS_A18") (pintype "power_in"))
      (node (ref "U5") (pin "F8") (pinfunction "VSS_F8") (pintype "power_in"))
      (node (ref "U5") (pin "G11") (pinfunction "VSS_G11") (pintype "power_in"))
      (node (ref "U5") (pin "G12") (pinfunction "VSS_G12") (pintype "power_in"))
      (node (ref "U5") (pin "G8") (pinfunction "VSS_G8") (pintype "power_in"))
      (node (ref "U5") (pin "G9") (pinfunction "VSS_G9") (pintype "power_in"))
      (node (ref "U5") (pin "H10") (pinfunction "VSS_H10") (pintype "power_in"))
      (node (ref "U5") (pin "H12") (pinfunction "VSS_H12") (pintype "power_in"))
      (node (ref "U5") (pin "H6") (pinfunction "VSS_H6") (pintype "power_in"))
      (node (ref "U5") (pin "H7") (pinfunction "VSS_H7") (pintype "power_in"))
      (node (ref "U5") (pin "H8") (pinfunction "VSS_H8") (pintype "power_in"))
      (node (ref "U5") (pin "H9") (pinfunction "VSS_H9") (pintype "power_in"))
      (node (ref "U5") (pin "J10") (pinfunction "VSS_J10") (pintype "power_in"))
      (node (ref "U5") (pin "J11") (pinfunction "VSS_J11") (pintype "power_in"))
      (node (ref "U5") (pin "J6") (pinfunction "VSS_J6") (pintype "power_in"))
      (node (ref "U5") (pin "J7") (pinfunction "VSS_J7") (pintype "power_in"))
      (node (ref "U5") (pin "J8") (pinfunction "VSS_J8") (pintype "power_in"))
      (node (ref "U5") (pin "J9") (pinfunction "VSS_J9") (pintype "power_in"))
      (node (ref "U5") (pin "K10") (pinfunction "VSS_K10") (pintype "power_in"))
      (node (ref "U5") (pin "K11") (pinfunction "VSS_K11") (pintype "power_in"))
      (node (ref "U5") (pin "K7") (pinfunction "VSS_K7") (pintype "power_in"))
      (node (ref "U5") (pin "K9") (pinfunction "VSS_K9") (pintype "power_in"))
      (node (ref "U5") (pin "L10") (pinfunction "VSS_L10") (pintype "power_in"))
      (node (ref "U5") (pin "L11") (pinfunction "VSS_L11") (pintype "power_in"))
      (node (ref "U5") (pin "L12") (pinfunction "VSS_L12") (pintype "power_in"))
      (node (ref "U5") (pin "L13") (pinfunction "VSS_L13") (pintype "power_in"))
      (node (ref "U5") (pin "M10") (pinfunction "VSS_M10") (pintype "power_in"))
      (node (ref "U5") (pin "M12") (pinfunction "VSS_M12") (pintype "power_in"))
      (node (ref "U5") (pin "M14") (pinfunction "VSSA_USB_M14") (pintype "power_in"))
      (node (ref "U5") (pin "M6") (pinfunction "VSS_M6") (pintype "power_in"))
      (node (ref "U5") (pin "M7") (pinfunction "VSS_M7") (pintype "power_in"))
      (node (ref "U5") (pin "M8") (pinfunction "VSS_M8") (pintype "power_in"))
      (node (ref "U5") (pin "M9") (pinfunction "VSS_M9") (pintype "power_in"))
      (node (ref "U5") (pin "N10") (pinfunction "VSS_N10") (pintype "power_in"))
      (node (ref "U5") (pin "N11") (pinfunction "VSS_N11") (pintype "power_in"))
      (node (ref "U5") (pin "N14") (pinfunction "VSSA_USB_N14") (pintype "power_in"))
      (node (ref "U5") (pin "N7") (pinfunction "VSS_N7") (pintype "power_in"))
      (node (ref "U5") (pin "V1") (pinfunction "VSS_V1") (pintype "power_in"))
      (node (ref "U5") (pin "V18") (pinfunction "VSS_V18") (pintype "power_in"))
    )
    (net (code "9") (name "GNDA_ADC") (class "Default")
      (node (ref "C93") (pin "2") (pinfunction "2_2") (pintype "passive"))
      (node (ref "FB3") (pin "1") (pinfunction "1_1") (pintype "passive"))
      (node (ref "U5") (pin "E8") (pinfunction "VSSA_ADC_E8") (pintype "power_in"))
    )
    (net (code "10") (name "VDDS") (class "Default")
      (node (ref "C80") (pin "1") (pinfunction "1_1") (pintype "passive"))
      (node (ref "C81") (pin "1") (pinfunction "1_1") (pintype "passive"))
      (node (ref "C82") (pin "1") (pinfunction "1_1") (pintype "passive"))
      (node (ref "C83") (pin "1") (pinfunction "1_1") (pintype "passive"))
      (node (ref "C84") (pin "1") (pinfunction "1_1") (pintype "passive"))
      (node (ref "C85") (pin "1") (pinfunction "1_1") (pintype "passive"))
      (node (ref "U5") (pin "E14") (pinfunction "VDDS_E14") (pintype "power_in"))
      (node (ref "U5") (pin "E6") (pinfunction "VDDS_E6") (pintype "power_in"))
      (node (ref "U5") (pin "F9") (pinfunction "VDDS_F9") (pintype "power_in"))
      (node (ref "U5") (pin "K13") (pinfunction "VDDS_K13") (pintype "power_in"))
      (node (ref "U5") (pin "N6") (pinfunction "VDDS_N6") (pintype "power_in"))
      (node (ref "U5") (pin "P14") (pinfunction "VDDS_P14") (pintype "power_in"))
      (node (ref "U5") (pin "P9") (pinfunction "VDDS_P9") (pintype "power_in"))
    )
    (net (code "11") (name "VDDS_DDR") (class "Default")
      (node (ref "C100") (pin "1") (pinfunction "1_1") (pintype "passive"))
      (node (ref "C101") (pin "1") (pinfunction "1_1") (pintype "passive"))
      (node (ref "C102") (pin "1") (pinfunction "1_1") (pintype "passive"))
      (node (ref "C103") (pin "1") (pinfunction "1_1") (pintype "passive"))
      (node (ref "C95") (pin "2") (pinfunction "2_2") (pintype "passive"))
      (node (ref "C96") (pin "2") (pinfunction "2_2") (pintype "passive"))
      (node (ref "C97") (pin "1") (pinfunction "1_1") (pintype "passive"))
      (node (ref "C98") (pin "1") (pinfunction "1_1") (pintype "passive"))
      (node (ref "C99") (pin "1") (pinfunction "1_1") (pintype "passive"))
      (node (ref "U5") (pin "E5") (pinfunction "VDDS_DDR_E5") (pintype "power_in"))
      (node (ref "U5") (pin "F5") (pinfunction "VDDS_DDR_F5") (pintype "power_in"))
      (node (ref "U5") (pin "G5") (pinfunction "VDDS_DDR_G5") (pintype "power_in"))
      (node (ref "U5") (pin "H5") (pinfunction "VDDS_DDR_H5") (pintype "power_in"))
      (node (ref "U5") (pin "J5") (pinfunction "VDDS_DDR_J5") (pintype "power_in"))
      (node (ref "U5") (pin "K5") (pinfunction "VDDS_DDR_K5") (pintype "power_in"))
      (node (ref "U5") (pin "L5") (pinfunction "VDDS_DDR_L5") (pintype "power_in"))
    )
    (net (code "12") (name "VDD_1V8") (class "Default")
      (node (ref "C78") (pin "1") (pinfunction "1_1") (pintype "passive"))
      (node (ref "C86") (pin "1") (pinfunction "1_1") (pintype "passive"))
      (node (ref "C88") (pin "1") (pinfunction "1_1") (pintype "passive"))
      (node (ref "FB1") (pin "1") (pinfunction "1_1") (pintype "passive"))
      (node (ref "FB2") (pin "2") (pinfunction "2_2") (pintype "passive"))
      (node (ref "U5") (pin "D10") (pinfunction "VDDS_SRAM_MPU_BB_D10") (pintype "power_in"))
      (node (ref "U5") (pin "E9") (pinfunction "VDDS_SRAM_CORE_BG_E9") (pintype "power_in"))
      (node (ref "U5") (pin "N16") (pinfunction "VDDA1P8V_USB0_N16") (pintype "power_in"))
      (node (ref "U5") (pin "R16") (pinfunction "VDDA1P8V_USB1_R16") (pintype "power_in"))
    )
    (net (code "13") (name "VDD_3V3A") (class "Default")
      (node (ref "C37") (pin "1") (pinfunction "1_1") (pintype "passive"))
      (node (ref "C38") (pin "1") (pinfunction "1_1") (pintype "passive"))
      (node (ref "C56") (pin "2") (pinfunction "2_2") (pintype "passive"))
      (node (ref "C57") (pin "2") (pinfunction "2_2") (pintype "passive"))
      (node (ref "C58") (pin "1") (pinfunction "1_1") (pintype "passive"))
      (node (ref "C59") (pin "1") (pinfunction "1_1") (pintype "passive"))
      (node (ref "C60") (pin "2") (pinfunction "2_2") (pintype "passive"))
      (node (ref "C61") (pin "2") (pinfunction "2_2") (pintype "passive"))
      (node (ref "C66") (pin "1") (pinfunction "1_1") (pintype "passive"))
      (node (ref "C67") (pin "1") (pinfunction "1_1") (pintype "passive"))
      (node (ref "C68") (pin "2") (pinfunction "2_2") (pintype "passive"))
      (node (ref "C69") (pin "2") (pinfunction "2_2") (pintype "passive"))
      (node (ref "C70") (pin "2") (pinfunction "2_2") (pintype "passive"))
      (node (ref "C71") (pin "2") (pinfunction "2_2") (pintype "passive"))
      (node (ref "C72") (pin "2") (pinfunction "2_2") (pintype "passive"))
      (node (ref "C73") (pin "2") (pinfunction "2_2") (pintype "passive"))
      (node (ref "C74") (pin "2") (pinfunction "2_2") (pintype "passive"))
      (node (ref "C75") (pin "2") (pinfunction "2_2") (pintype "passive"))
      (node (ref "C76") (pin "2") (pinfunction "2_2") (pintype "passive"))
      (node (ref "C77") (pin "1") (pinfunction "1_1") (pintype "passive"))
      (node (ref "C87") (pin "1") (pinfunction "1_1") (pintype "passive"))
      (node (ref "U5") (pin "E10") (pinfunction "VDDSHV6_E10") (pintype "power_in"))
      (node (ref "U5") (pin "E11") (pinfunction "VDDSHV6_E11") (pintype "power_in"))
      (node (ref "U5") (pin "E12") (pinfunction "VDDSHV6_E12") (pintype "power_in"))
      (node (ref "U5") (pin "E13") (pinfunction "VDDSHV6_E13") (pintype "power_in"))
      (node (ref "U5") (pin "F14") (pinfunction "VDDSHV6_F14") (pintype "power_in"))
      (node (ref "U5") (pin "G14") (pinfunction "VDDSHV6_G14") (pintype "power_in"))
      (node (ref "U5") (pin "H14") (pinfunction "VDDSHV4_H14") (pintype "power_in"))
      (node (ref "U5") (pin "J14") (pinfunction "VDDSHV4_J14") (pintype "power_in"))
      (node (ref "U5") (pin "K14") (pinfunction "VDDSHV5_K14") (pintype "power_in"))
      (node (ref "U5") (pin "L14") (pinfunction "VDDSHV5_L14") (pintype "power_in"))
      (node (ref "U5") (pin "N15") (pinfunction "VDDA3P3V_USB0_N15") (pintype "power_in"))
      (node (ref "U5") (pin "N5") (pinfunction "VDDSHV6_N5") (pintype "power_in"))
      (node (ref "U5") (pin "P10") (pinfunction "VDDSHV2_P10") (pintype "power_in"))
      (node (ref "U5") (pin "P11") (pinfunction "VDDSHV2_P11") (pintype "power_in"))
      (node (ref "U5") (pin "P12") (pinfunction "VDDSHV3_P12") (pintype "power_in"))
      (node (ref "U5") (pin "P13") (pinfunction "VDDSHV3_P13") (pintype "power_in"))
      (node (ref "U5") (pin "P5") (pinfunction "VDDSHV6_P5") (pintype "power_in"))
      (node (ref "U5") (pin "P6") (pinfunction "VDDSHV6_P6") (pintype "power_in"))
      (node (ref "U5") (pin "P7") (pinfunction "VDDSHV1_P7") (pintype "power_in"))
      (node (ref "U5") (pin "P8") (pinfunction "VDDSHV1_P8") (pintype "power_in"))
      (node (ref "U5") (pin "R15") (pinfunction "VDDA3P3V_USB1_R15") (pintype "power_in"))
    )
    (net (code "14") (name "VDD_ADC") (class "Default")
      (node (ref "C93") (pin "1") (pinfunction "1_1") (pintype "passive"))
      (node (ref "FB2") (pin "1") (pinfunction "1_1") (pintype "passive"))
      (node (ref "U5") (pin "D8") (pinfunction "VDDA_ADC_D8") (pintype "power_in"))
    )
    (net (code "15") (name "VDD_CORE") (class "Default")
      (node (ref "C39") (pin "2") (pinfunction "2_2") (pintype "passive"))
      (node (ref "C40") (pin "2") (pinfunction "2_2") (pintype "passive"))
      (node (ref "C41") (pin "1") (pinfunction "1_1") (pintype "passive"))
      (node (ref "C42") (pin "1") (pinfunction "1_1") (pintype "passive"))
      (node (ref "C43") (pin "1") (pinfunction "1_1") (pintype "passive"))
      (node (ref "C44") (pin "1") (pinfunction "1_1") (pintype "passive"))
      (node (ref "C45") (pin "1") (pinfunction "1_1") (pintype "passive"))
      (node (ref "C46") (pin "1") (pinfunction "1_1") (pintype "passive"))
      (node (ref "C47") (pin "1") (pinfunction "1_1") (pintype "passive"))
      (node (ref "C48") (pin "1") (pinfunction "1_1") (pintype "passive"))
      (node (ref "C49") (pin "1") (pinfunction "1_1") (pintype "passive"))
      (node (ref "C50") (pin "1") (pinfunction "1_1") (pintype "passive"))
      (node (ref "C51") (pin "1") (pinfunction "1_1") (pintype "passive"))
      (node (ref "C52") (pin "1") (pinfunction "1_1") (pintype "passive"))
      (node (ref "C53") (pin "1") (pinfunction "1_1") (pintype "passive"))
      (node (ref "C54") (pin "1") (pinfunction "1_1") (pintype "passive"))
      (node (ref "C55") (pin "2") (pinfunction "2_2") (pintype "passive"))
      (node (ref "U5") (pin "F6") (pinfunction "VDD_CORE1_F6") (pintype "power_in"))
      (node (ref "U5") (pin "F7") (pinfunction "VDD_CORE2_F7") (pintype "power_in"))
      (node (ref "U5") (pin "G10") (pinfunction "VDD_CORE5_G10") (pintype "power_in"))
      (node (ref "U5") (pin "G6") (pinfunction "VDD_CORE3_G6") (pintype "power_in"))
      (node (ref "U5") (pin "G7") (pinfunction "VDD_CORE4_G7") (pintype "power_in"))
      (node (ref "U5") (pin "H11") (pinfunction "VDD_CORE6_H11") (pintype "power_in"))
      (node (ref "U5") (pin "J12") (pinfunction "VDD_CORE7_J12") (pintype "power_in"))
      (node (ref "U5") (pin "K12") (pinfunction "VDD_CORE10_K12") (pintype "power_in"))
      (node (ref "U5") (pin "K6") (pinfunction "VDD_CORE8_K6") (pintype "power_in"))
      (node (ref "U5") (pin "K8") (pinfunction "VDD_CORE9_K8") (pintype "power_in"))
      (node (ref "U5") (pin "L6") (pinfunction "VDD_CORE11_L6") (pintype "power_in"))
      (node (ref "U5") (pin "L7") (pinfunction "VDD_CORE12_L7") (pintype "power_in"))
      (node (ref "U5") (pin "L8") (pinfunction "VDD_CORE13_L8") (pintype "power_in"))
      (node (ref "U5") (pin "L9") (pinfunction "VDD_CORE14_L9") (pintype "power_in"))
      (node (ref "U5") (pin "M11") (pinfunction "VDD_CORE15_M11") (pintype "power_in"))
      (node (ref "U5") (pin "M13") (pinfunction "VDD_CORE16_M13") (pintype "power_in"))
      (node (ref "U5") (pin "N12") (pinfunction "VDD_CORE19_N12") (pintype "power_in"))
      (node (ref "U5") (pin "N13") (pinfunction "VDD_CORE20_N13") (pintype "power_in"))
      (node (ref "U5") (pin "N8") (pinfunction "VDD_CORE17_N8") (pintype "power_in"))
      (node (ref "U5") (pin "N9") (pinfunction "VDD_CORE18_N9") (pintype "power_in"))
    )
    (net (code "16") (name "VDD_MPU") (class "Default")
      (node (ref "C62") (pin "2") (pinfunction "2_2") (pintype "passive"))
      (node (ref "C63") (pin "1") (pinfunction "1_1") (pintype "passive"))
      (node (ref "C64") (pin "1") (pinfunction "1_1") (pintype "passive"))
      (node (ref "C65") (pin "1") (pinfunction "1_1") (pintype "passive"))
      (node (ref "U5") (pin "F10") (pinfunction "VDD_MPU1_F10") (pintype "power_in"))
      (node (ref "U5") (pin "F11") (pinfunction "VDD_MPU2_F11") (pintype "power_in"))
      (node (ref "U5") (pin "F12") (pinfunction "VDD_MPU3_F12") (pintype "power_in"))
      (node (ref "U5") (pin "F13") (pinfunction "VDD_MPU4_F13") (pintype "power_in"))
      (node (ref "U5") (pin "G13") (pinfunction "VDD_MPU5_G13") (pintype "power_in"))
      (node (ref "U5") (pin "H13") (pinfunction "VDD_MPU6_H13") (pintype "power_in"))
      (node (ref "U5") (pin "J13") (pinfunction "VDD_MPU7_J13") (pintype "power_in"))
    )
    (net (code "17") (name "VDD_PLL") (class "Default")
      (node (ref "C106") (pin "1") (pinfunction "1_1") (pintype "passive"))
      (node (ref "C79") (pin "1") (pinfunction "1_1") (pintype "passive"))
      (node (ref "C92") (pin "1") (pinfunction "1_1") (pintype "passive"))
      (node (ref "C94") (pin "1") (pinfunction "1_1") (pintype "passive"))
      (node (ref "FB1") (pin "2") (pinfunction "2_2") (pintype "passive"))
      (node (ref "U5") (pin "E7") (pinfunction "VDDS_PLL_DDR_E7") (pintype "power_in"))
      (node (ref "U5") (pin "H15") (pinfunction "VDDS_PLL_MPU_H15") (pintype "power_in"))
      (node (ref "U5") (pin "R10") (pinfunction "VDDS_PLL_CORE_LCD_R10") (pintype "power_in"))
      (node (ref "U5") (pin "R11") (pinfunction "VDDS_OSC_R11") (pintype "power_in"))
    )
    (net (code "18") (name "VRTC") (class "Default")
      (node (ref "C105") (pin "1") (pinfunction "1_1") (pintype "passive"))
      (node (ref "U5") (pin "D7") (pinfunction "VDDS_RTC_D7") (pintype "power_in"))
    )
    (net (code "19") (name "unconnected-(U5C-VPP-PadM5)") (class "Default")
      (node (ref "U5") (pin "M5") (pinfunction "VPP_M5") (pintype "power_in+no_connect"))
    )
  )
)
